# Electrochemical_sensors.net
KiCad netlist of a schematic drawn in Altium Designer
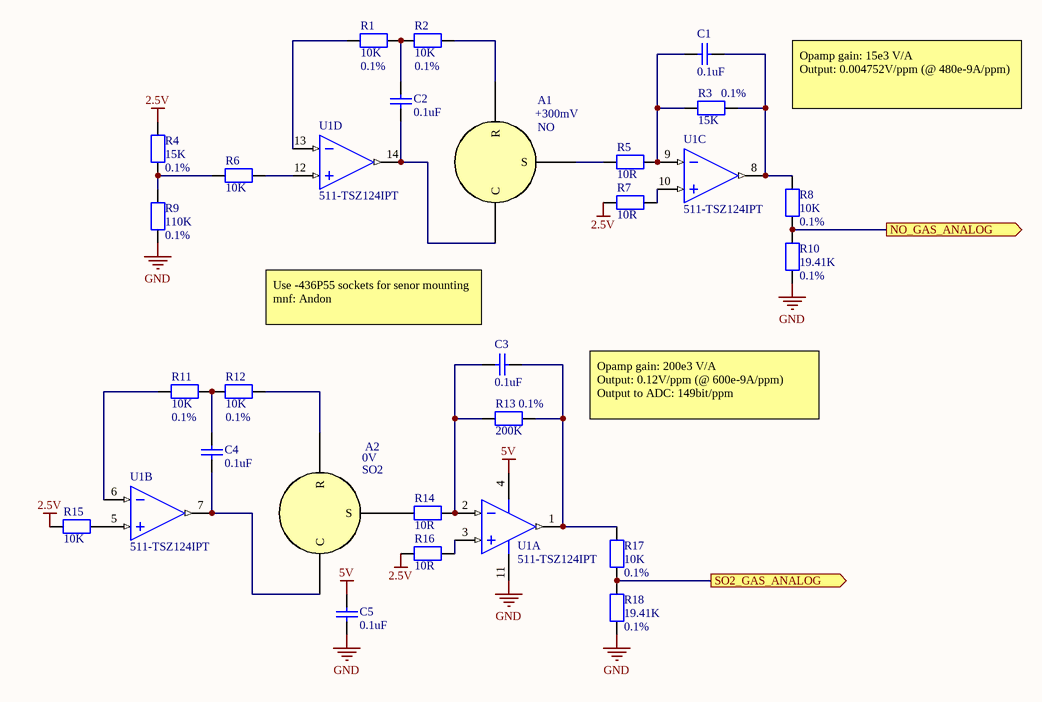
[diagram p0: Electrochemical_sensors.SchDoc]

(export (version "E")
  (design (tool "Eeschema 10.0.6"))
  (components
    (comp (ref "A1")
      (value "Electrochemical sensors")
      (footprint "Electrochemical")
      (fields (field (name "GAS_TYPE") "NO") (field (name "POTENTIAL") "+300mV"))
      (libsource (lib "Sensors") (part "Electrochemical_sensor"))
    )
    (comp (ref "A2")
      (value "Electrochemical sensors")
      (footprint "Electrochemical")
      (fields (field (name "GAS_TYPE") "SO2") (field (name "PTENTIAL") "0V"))
      (libsource (lib "Sensors") (part "Electrochemical_sensor"))
    )
    (comp (ref "C1")
      (value "0.1uF")
      (footprint "0603_CAP")
      (fields (field (name "Comment") "Capacitor"))
      (libsource (lib "Passive_comp") (part "Capacitor"))
    )
    (comp (ref "C2")
      (value "0.1uF")
      (footprint "0603_CAP")
      (fields (field (name "Comment") "Capacitor"))
      (libsource (lib "Passive_comp") (part "Capacitor"))
    )
    (comp (ref "C3")
      (value "0.1uF")
      (footprint "0603_CAP")
      (fields (field (name "Comment") "Capacitor"))
      (libsource (lib "Passive_comp") (part "Capacitor"))
    )
    (comp (ref "C4")
      (value "0.1uF")
      (footprint "0603_CAP")
      (fields (field (name "Comment") "Capacitor"))
      (libsource (lib "Passive_comp") (part "Capacitor"))
    )
    (comp (ref "C5")
      (value "0.1uF")
      (footprint "0603_CAP")
      (fields (field (name "Comment") "Capacitor"))
      (libsource (lib "Passive_comp") (part "Capacitor"))
    )
    (comp (ref "R1")
      (value "10K")
      (footprint "0603_RES")
      (fields (field (name "ACCURACY") "0.1%") (field (name "Comment") "Resitor"))
      (libsource (lib "") (part "Resitor_1"))
    )
    (comp (ref "R2")
      (value "10K")
      (footprint "0603_RES")
      (fields (field (name "ACCURACY") "0.1%") (field (name "Comment") "Resitor"))
      (libsource (lib "") (part "Resitor_1"))
    )
    (comp (ref "R3")
      (value "15K")
      (footprint "0603_RES")
      (fields (field (name "ACCURACY") "0.1%") (field (name "Comment") "Resitor"))
      (libsource (lib "") (part "Resitor_1"))
    )
    (comp (ref "R4")
      (value "15K")
      (footprint "0603_RES")
      (fields (field (name "ACCURACY") "0.1%") (field (name "Comment") "Resitor"))
      (libsource (lib "Passive_comp") (part "Resitor"))
    )
    (comp (ref "R5")
      (value "10R")
      (footprint "0603_RES")
      (fields (field (name "Comment") "Resitor"))
      (libsource (lib "") (part "Resitor_2"))
    )
    (comp (ref "R6")
      (value "10K")
      (footprint "0603_RES")
      (fields (field (name "Comment") "Resitor"))
      (libsource (lib "") (part "Resitor_2"))
    )
    (comp (ref "R7")
      (value "10R")
      (footprint "0603_RES")
      (fields (field (name "Comment") "Resitor"))
      (libsource (lib "") (part "Resitor_2"))
    )
    (comp (ref "R8")
      (value "10K")
      (footprint "0603_RES")
      (fields (field (name "ACCURACY") "0.1%") (field (name "Comment") "Resitor"))
      (libsource (lib "Passive_comp") (part "Resitor"))
    )
    (comp (ref "R9")
      (value "110K")
      (footprint "0603_RES")
      (fields (field (name "ACCURACY") "0.1%") (field (name "Comment") "Resitor"))
      (libsource (lib "Passive_comp") (part "Resitor"))
    )
    (comp (ref "R10")
      (value "19.41K")
      (footprint "0603_RES")
      (fields (field (name "ACCURACY") "0.1%") (field (name "Comment") "Resitor"))
      (libsource (lib "Passive_comp") (part "Resitor"))
    )
    (comp (ref "R11")
      (value "10K")
      (footprint "0603_RES")
      (fields (field (name "ACCURACY") "0.1%") (field (name "Comment") "Resitor"))
      (libsource (lib "") (part "Resitor_1"))
    )
    (comp (ref "R12")
      (value "10K")
      (footprint "0603_RES")
      (fields (field (name "ACCURACY") "0.1%") (field (name "Comment") "Resitor"))
      (libsource (lib "") (part "Resitor_1"))
    )
    (comp (ref "R13")
      (value "200K")
      (footprint "0603_RES")
      (fields (field (name "ACCURACY") "0.1%") (field (name "Comment") "Resitor"))
      (libsource (lib "") (part "Resitor_1"))
    )
    (comp (ref "R14")
      (value "10R")
      (footprint "0603_RES")
      (fields (field (name "Comment") "Resitor"))
      (libsource (lib "") (part "Resitor_2"))
    )
    (comp (ref "R15")
      (value "10K")
      (footprint "0603_RES")
      (fields (field (name "Comment") "Resitor"))
      (libsource (lib "") (part "Resitor_2"))
    )
    (comp (ref "R16")
      (value "10R")
      (footprint "0603_RES")
      (fields (field (name "Comment") "Resitor"))
      (libsource (lib "") (part "Resitor_2"))
    )
    (comp (ref "R17")
      (value "10K")
      (footprint "0603_RES")
      (fields (field (name "ACCURACY") "0.1%") (field (name "Comment") "Resitor"))
      (libsource (lib "Passive_comp") (part "Resitor"))
    )
    (comp (ref "R18")
      (value "19.41K")
      (footprint "0603_RES")
      (fields (field (name "ACCURACY") "0.1%") (field (name "Comment") "Resitor"))
      (libsource (lib "Passive_comp") (part "Resitor"))
    )
    (comp (ref "U1")
      (value "TSZ124")
      (footprint "TSOP65P640X120-14M")
      (fields (field (name "SUPPLIER PART NUMBER 1") "511-TSZ124IPT"))
      (libsource (lib "stm") (part "TSZ124"))
    )
  )
  (nets
    (net (code "1") (name "/NO_GAS_ANALOG") (class "Default")
      (node (ref "R10") (pin "2") (pinfunction "2_2") (pintype "passive"))
      (node (ref "R8") (pin "1") (pinfunction "1_1") (pintype "passive"))
    )
    (net (code "2") (name "/SO2_GAS_ANALOG") (class "Default")
      (node (ref "R17") (pin "1") (pinfunction "1_1") (pintype "passive"))
      (node (ref "R18") (pin "2") (pinfunction "2_2") (pintype "passive"))
    )
    (net (code "3") (name "2.5V") (class "Default")
      (node (ref "R15") (pin "1") (pinfunction "1_1") (pintype "passive"))
      (node (ref "R16") (pin "1") (pinfunction "1_1") (pintype "passive"))
      (node (ref "R4") (pin "2") (pinfunction "2_2") (pintype "passive"))
      (node (ref "R7") (pin "1") (pinfunction "1_1") (pintype "passive"))
    )
    (net (code "4") (name "5V") (class "Default")
      (node (ref "C5") (pin "2") (pinfunction "2_2") (pintype "passive"))
      (node (ref "U1") (pin "4") (pinfunction "V+_4") (pintype "power_in"))
    )
    (net (code "5") (name "GND") (class "Default")
      (node (ref "C5") (pin "1") (pinfunction "1_1") (pintype "passive"))
      (node (ref "R10") (pin "1") (pinfunction "1_1") (pintype "passive"))
      (node (ref "R18") (pin "1") (pinfunction "1_1") (pintype "passive"))
      (node (ref "R9") (pin "1") (pinfunction "1_1") (pintype "passive"))
      (node (ref "U1") (pin "11") (pinfunction "V-_11") (pintype "power_in"))
    )
    (net (code "6") (name "Net-(A1-PadR)") (class "Default")
      (node (ref "A1") (pin "R") (pinfunction "R_R") (pintype "passive"))
      (node (ref "R2") (pin "1") (pinfunction "1_1") (pintype "passive"))
    )
    (net (code "7") (name "Net-(A1-PadS)") (class "Default")
      (node (ref "A1") (pin "S") (pinfunction "S_S") (pintype "passive"))
      (node (ref "R5") (pin "1") (pinfunction "1_1") (pintype "passive"))
    )
    (net (code "8") (name "Net-(A2-PadR)") (class "Default")
      (node (ref "A2") (pin "R") (pinfunction "R_R") (pintype "passive"))
      (node (ref "R12") (pin "1") (pinfunction "1_1") (pintype "passive"))
    )
    (net (code "9") (name "Net-(A2-PadS)") (class "Default")
      (node (ref "A2") (pin "S") (pinfunction "S_S") (pintype "passive"))
      (node (ref "R14") (pin "1") (pinfunction "1_1") (pintype "passive"))
    )
    (net (code "10") (name "Net-(C2-Pad2)") (class "Default")
      (node (ref "C2") (pin "2") (pinfunction "2_2") (pintype "passive"))
      (node (ref "R1") (pin "1") (pinfunction "1_1") (pintype "passive"))
      (node (ref "R2") (pin "2") (pinfunction "2_2") (pintype "passive"))
    )
    (net (code "11") (name "Net-(C4-Pad2)") (class "Default")
      (node (ref "C4") (pin "2") (pinfunction "2_2") (pintype "passive"))
      (node (ref "R11") (pin "1") (pinfunction "1_1") (pintype "passive"))
      (node (ref "R12") (pin "2") (pinfunction "2_2") (pintype "passive"))
    )
    (net (code "12") (name "Net-(R4-Pad1)") (class "Default")
      (node (ref "R4") (pin "1") (pinfunction "1_1") (pintype "passive"))
      (node (ref "R6") (pin "1") (pinfunction "1_1") (pintype "passive"))
      (node (ref "R9") (pin "2") (pinfunction "2_2") (pintype "passive"))
    )
    (net (code "13") (name "Net-(U1A-IN1+)") (class "Default")
      (node (ref "R16") (pin "2") (pinfunction "2_2") (pintype "passive"))
      (node (ref "U1") (pin "3") (pinfunction "IN1+_3") (pintype "input"))
    )
    (net (code "14") (name "Net-(U1A-IN1-)") (class "Default")
      (node (ref "C3") (pin "2") (pinfunction "2_2") (pintype "passive"))
      (node (ref "R13") (pin "2") (pinfunction "2_2") (pintype "passive"))
      (node (ref "R14") (pin "2") (pinfunction "2_2") (pintype "passive"))
      (node (ref "U1") (pin "2") (pinfunction "IN1-_2") (pintype "input"))
    )
    (net (code "15") (name "Net-(U1A-OUT1)") (class "Default")
      (node (ref "C3") (pin "1") (pinfunction "1_1") (pintype "passive"))
      (node (ref "R13") (pin "1") (pinfunction "1_1") (pintype "passive"))
      (node (ref "R17") (pin "2") (pinfunction "2_2") (pintype "passive"))
      (node (ref "U1") (pin "1") (pinfunction "OUT1_1") (pintype "output"))
    )
    (net (code "16") (name "Net-(U1B-IN2+)") (class "Default")
      (node (ref "R15") (pin "2") (pinfunction "2_2") (pintype "passive"))
      (node (ref "U1") (pin "5") (pinfunction "IN2+_5") (pintype "input"))
    )
    (net (code "17") (name "Net-(U1B-IN2-)") (class "Default")
      (node (ref "R11") (pin "2") (pinfunction "2_2") (pintype "passive"))
      (node (ref "U1") (pin "6") (pinfunction "IN2-_6") (pintype "input"))
    )
    (net (code "18") (name "Net-(U1B-OUT2)") (class "Default")
      (node (ref "A2") (pin "C") (pinfunction "C_C") (pintype "passive"))
      (node (ref "C4") (pin "1") (pinfunction "1_1") (pintype "passive"))
      (node (ref "U1") (pin "7") (pinfunction "OUT2_7") (pintype "output"))
    )
    (net (code "19") (name "Net-(U1C-IN3+)") (class "Default")
      (node (ref "R7") (pin "2") (pinfunction "2_2") (pintype "passive"))
      (node (ref "U1") (pin "10") (pinfunction "IN3+_10") (pintype "input"))
    )
    (net (code "20") (name "Net-(U1C-IN3-)") (class "Default")
      (node (ref "C1") (pin "2") (pinfunction "2_2") (pintype "passive"))
      (node (ref "R3") (pin "2") (pinfunction "2_2") (pintype "passive"))
      (node (ref "R5") (pin "2") (pinfunction "2_2") (pintype "passive"))
      (node (ref "U1") (pin "9") (pinfunction "IN3-_9") (pintype "input"))
    )
    (net (code "21") (name "Net-(U1C-OUT3)") (class "Default")
      (node (ref "C1") (pin "1") (pinfunction "1_1") (pintype "passive"))
      (node (ref "R3") (pin "1") (pinfunction "1_1") (pintype "passive"))
      (node (ref "R8") (pin "2") (pinfunction "2_2") (pintype "passive"))
      (node (ref "U1") (pin "8") (pinfunction "OUT3_8") (pintype "output"))
    )
    (net (code "22") (name "Net-(U1D-IN4+)") (class "Default")
      (node (ref "R6") (pin "2") (pinfunction "2_2") (pintype "passive"))
      (node (ref "U1") (pin "12") (pinfunction "IN4+_12") (pintype "input"))
    )
    (net (code "23") (name "Net-(U1D-IN4-)") (class "Default")
      (node (ref "R1") (pin "2") (pinfunction "2_2") (pintype "passive"))
      (node (ref "U1") (pin "13") (pinfunction "IN4-_13") (pintype "input"))
    )
    (net (code "24") (name "Net-(U1D-OUT4)") (class "Default")
      (node (ref "A1") (pin "C") (pinfunction "C_C") (pintype "passive"))
      (node (ref "C2") (pin "1") (pinfunction "1_1") (pintype "passive"))
      (node (ref "U1") (pin "14") (pinfunction "OUT4_14") (pintype "output"))
    )
  )
)
